# RGB_LEDs.net
KiCad netlist of a schematic drawn in Altium Designer
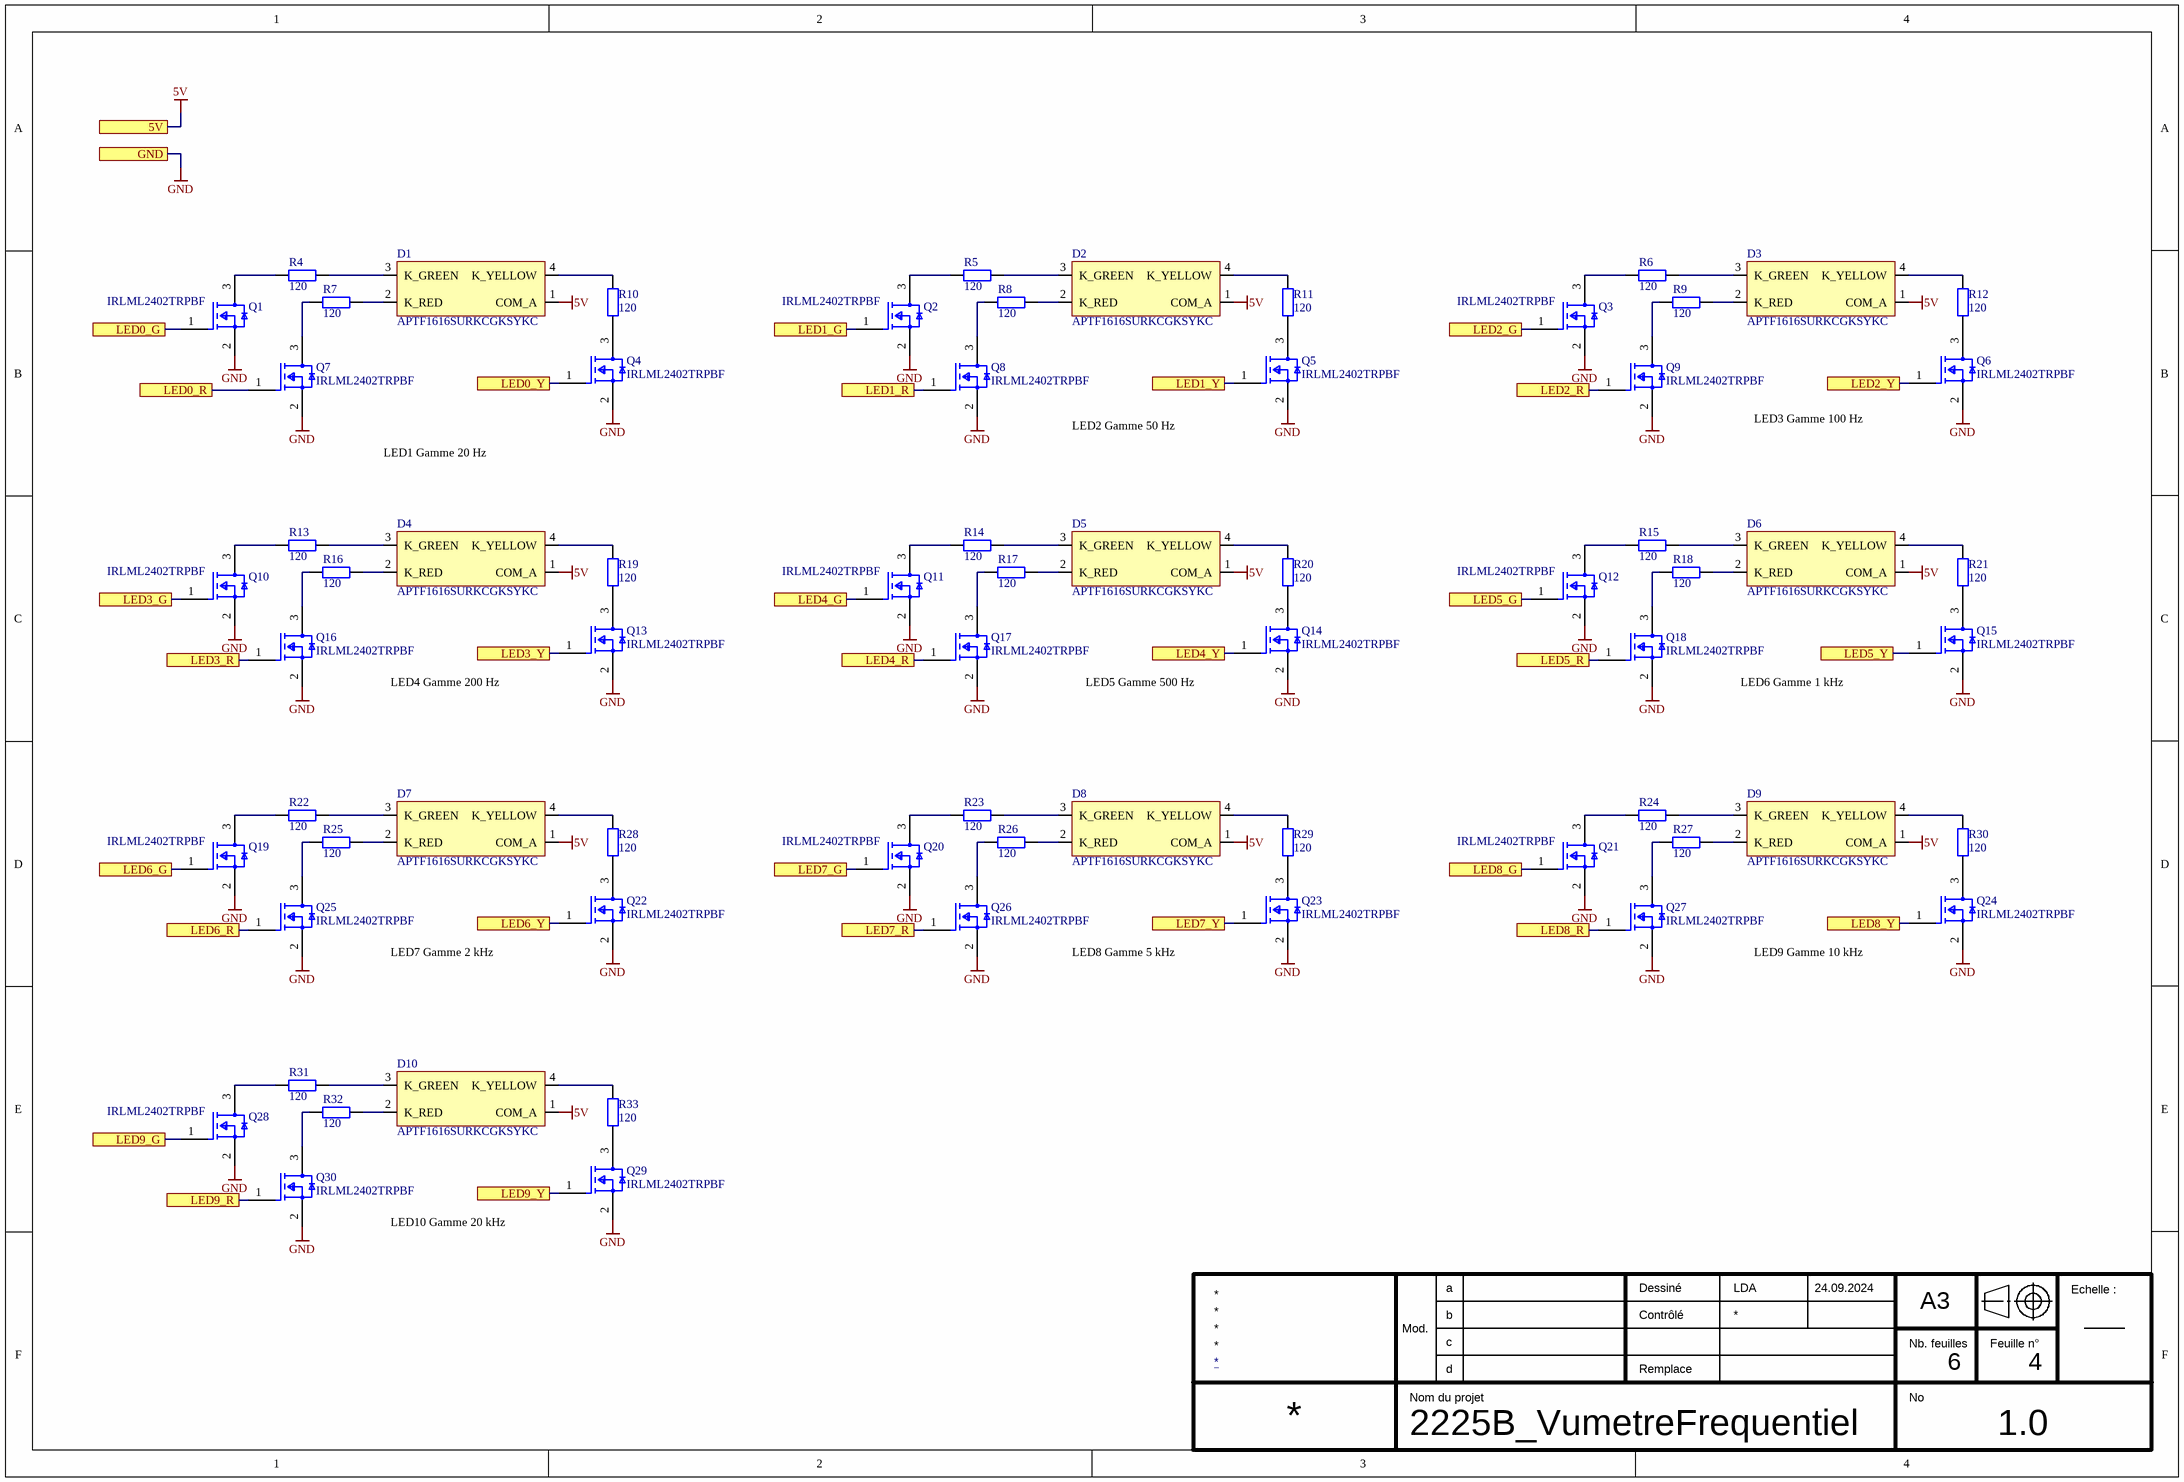
[diagram p0: RGB_LEDs.SchDoc]

(export (version "E")
  (design (tool "Eeschema 10.0.6"))
  (components
    (comp (ref "D1")
      (value "APTF1616SURKCGKSYKC")
      (footprint "APTF1616SURKCGKSYKC")
      (fields (field (name "MOUSER PART NUMBER") "604-APTF1616KCGKSYKC"))
      (libsource (lib "2225B_VumetreFrequenciel") (part "APTF1616SURKCGKSYKC"))
    )
    (comp (ref "D2")
      (value "APTF1616SURKCGKSYKC")
      (footprint "APTF1616SURKCGKSYKC")
      (fields (field (name "MOUSER PART NUMBER") "604-APTF1616KCGKSYKC"))
      (libsource (lib "2225B_VumetreFrequenciel") (part "APTF1616SURKCGKSYKC"))
    )
    (comp (ref "D3")
      (value "APTF1616SURKCGKSYKC")
      (footprint "APTF1616SURKCGKSYKC")
      (fields (field (name "MOUSER PART NUMBER") "604-APTF1616KCGKSYKC"))
      (libsource (lib "2225B_VumetreFrequenciel") (part "APTF1616SURKCGKSYKC"))
    )
    (comp (ref "D4")
      (value "APTF1616SURKCGKSYKC")
      (footprint "APTF1616SURKCGKSYKC")
      (fields (field (name "MOUSER PART NUMBER") "604-APTF1616KCGKSYKC"))
      (libsource (lib "2225B_VumetreFrequenciel") (part "APTF1616SURKCGKSYKC"))
    )
    (comp (ref "D5")
      (value "APTF1616SURKCGKSYKC")
      (footprint "APTF1616SURKCGKSYKC")
      (fields (field (name "MOUSER PART NUMBER") "604-APTF1616KCGKSYKC"))
      (libsource (lib "2225B_VumetreFrequenciel") (part "APTF1616SURKCGKSYKC"))
    )
    (comp (ref "D6")
      (value "APTF1616SURKCGKSYKC")
      (footprint "APTF1616SURKCGKSYKC")
      (fields (field (name "MOUSER PART NUMBER") "604-APTF1616KCGKSYKC"))
      (libsource (lib "2225B_VumetreFrequenciel") (part "APTF1616SURKCGKSYKC"))
    )
    (comp (ref "D7")
      (value "APTF1616SURKCGKSYKC")
      (footprint "APTF1616SURKCGKSYKC")
      (fields (field (name "MOUSER PART NUMBER") "604-APTF1616KCGKSYKC"))
      (libsource (lib "2225B_VumetreFrequenciel") (part "APTF1616SURKCGKSYKC"))
    )
    (comp (ref "D8")
      (value "APTF1616SURKCGKSYKC")
      (footprint "APTF1616SURKCGKSYKC")
      (fields (field (name "MOUSER PART NUMBER") "604-APTF1616KCGKSYKC"))
      (libsource (lib "2225B_VumetreFrequenciel") (part "APTF1616SURKCGKSYKC"))
    )
    (comp (ref "D9")
      (value "APTF1616SURKCGKSYKC")
      (footprint "APTF1616SURKCGKSYKC")
      (fields (field (name "MOUSER PART NUMBER") "604-APTF1616KCGKSYKC"))
      (libsource (lib "2225B_VumetreFrequenciel") (part "APTF1616SURKCGKSYKC"))
    )
    (comp (ref "D10")
      (value "APTF1616SURKCGKSYKC")
      (footprint "APTF1616SURKCGKSYKC")
      (fields (field (name "MOUSER PART NUMBER") "604-APTF1616KCGKSYKC"))
      (libsource (lib "2225B_VumetreFrequenciel") (part "APTF1616SURKCGKSYKC"))
    )
    (comp (ref "Q1")
      (value "IRLML2402TRPBF")
      (footprint "FP-Micro3-IPC_B")
      (description "MOSFET N-CH 20V 1.2A SOT-23")
      (libsource (lib "Altium Content Vault") (part "0a9ea7c96deaaede766a5b531c28de0"))
    )
    (comp (ref "Q2")
      (value "IRLML2402TRPBF")
      (footprint "FP-Micro3-IPC_B")
      (description "MOSFET N-CH 20V 1.2A SOT-23")
      (libsource (lib "Altium Content Vault") (part "0a9ea7c96deaaede766a5b531c28de0"))
    )
    (comp (ref "Q3")
      (value "IRLML2402TRPBF")
      (footprint "FP-Micro3-IPC_B")
      (description "MOSFET N-CH 20V 1.2A SOT-23")
      (libsource (lib "Altium Content Vault") (part "0a9ea7c96deaaede766a5b531c28de0"))
    )
    (comp (ref "Q4")
      (value "IRLML2402TRPBF")
      (footprint "FP-Micro3-IPC_B")
      (description "MOSFET N-CH 20V 1.2A SOT-23")
      (libsource (lib "Altium Content Vault") (part "0a9ea7c96deaaede766a5b531c28de0"))
    )
    (comp (ref "Q5")
      (value "IRLML2402TRPBF")
      (footprint "FP-Micro3-IPC_B")
      (description "MOSFET N-CH 20V 1.2A SOT-23")
      (libsource (lib "Altium Content Vault") (part "0a9ea7c96deaaede766a5b531c28de0"))
    )
    (comp (ref "Q6")
      (value "IRLML2402TRPBF")
      (footprint "FP-Micro3-IPC_B")
      (description "MOSFET N-CH 20V 1.2A SOT-23")
      (libsource (lib "Altium Content Vault") (part "0a9ea7c96deaaede766a5b531c28de0"))
    )
    (comp (ref "Q7")
      (value "IRLML2402TRPBF")
      (footprint "FP-Micro3-IPC_B")
      (description "MOSFET N-CH 20V 1.2A SOT-23")
      (libsource (lib "Altium Content Vault") (part "0a9ea7c96deaaede766a5b531c28de0"))
    )
    (comp (ref "Q8")
      (value "IRLML2402TRPBF")
      (footprint "FP-Micro3-IPC_B")
      (description "MOSFET N-CH 20V 1.2A SOT-23")
      (libsource (lib "Altium Content Vault") (part "0a9ea7c96deaaede766a5b531c28de0"))
    )
    (comp (ref "Q9")
      (value "IRLML2402TRPBF")
      (footprint "FP-Micro3-IPC_B")
      (description "MOSFET N-CH 20V 1.2A SOT-23")
      (libsource (lib "Altium Content Vault") (part "0a9ea7c96deaaede766a5b531c28de0"))
    )
    (comp (ref "Q10")
      (value "IRLML2402TRPBF")
      (footprint "FP-Micro3-IPC_B")
      (description "MOSFET N-CH 20V 1.2A SOT-23")
      (libsource (lib "Altium Content Vault") (part "0a9ea7c96deaaede766a5b531c28de0"))
    )
    (comp (ref "Q11")
      (value "IRLML2402TRPBF")
      (footprint "FP-Micro3-IPC_B")
      (description "MOSFET N-CH 20V 1.2A SOT-23")
      (libsource (lib "Altium Content Vault") (part "0a9ea7c96deaaede766a5b531c28de0"))
    )
    (comp (ref "Q12")
      (value "IRLML2402TRPBF")
      (footprint "FP-Micro3-IPC_B")
      (description "MOSFET N-CH 20V 1.2A SOT-23")
      (libsource (lib "Altium Content Vault") (part "0a9ea7c96deaaede766a5b531c28de0"))
    )
    (comp (ref "Q13")
      (value "IRLML2402TRPBF")
      (footprint "FP-Micro3-IPC_B")
      (description "MOSFET N-CH 20V 1.2A SOT-23")
      (libsource (lib "Altium Content Vault") (part "0a9ea7c96deaaede766a5b531c28de0"))
    )
    (comp (ref "Q14")
      (value "IRLML2402TRPBF")
      (footprint "FP-Micro3-IPC_B")
      (description "MOSFET N-CH 20V 1.2A SOT-23")
      (libsource (lib "Altium Content Vault") (part "0a9ea7c96deaaede766a5b531c28de0"))
    )
    (comp (ref "Q15")
      (value "IRLML2402TRPBF")
      (footprint "FP-Micro3-IPC_B")
      (description "MOSFET N-CH 20V 1.2A SOT-23")
      (libsource (lib "Altium Content Vault") (part "0a9ea7c96deaaede766a5b531c28de0"))
    )
    (comp (ref "Q16")
      (value "IRLML2402TRPBF")
      (footprint "FP-Micro3-IPC_B")
      (description "MOSFET N-CH 20V 1.2A SOT-23")
      (libsource (lib "Altium Content Vault") (part "0a9ea7c96deaaede766a5b531c28de0"))
    )
    (comp (ref "Q17")
      (value "IRLML2402TRPBF")
      (footprint "FP-Micro3-IPC_B")
      (description "MOSFET N-CH 20V 1.2A SOT-23")
      (libsource (lib "Altium Content Vault") (part "0a9ea7c96deaaede766a5b531c28de0"))
    )
    (comp (ref "Q18")
      (value "IRLML2402TRPBF")
      (footprint "FP-Micro3-IPC_B")
      (description "MOSFET N-CH 20V 1.2A SOT-23")
      (libsource (lib "Altium Content Vault") (part "0a9ea7c96deaaede766a5b531c28de0"))
    )
    (comp (ref "Q19")
      (value "IRLML2402TRPBF")
      (footprint "FP-Micro3-IPC_B")
      (description "MOSFET N-CH 20V 1.2A SOT-23")
      (libsource (lib "Altium Content Vault") (part "0a9ea7c96deaaede766a5b531c28de0"))
    )
    (comp (ref "Q20")
      (value "IRLML2402TRPBF")
      (footprint "FP-Micro3-IPC_B")
      (description "MOSFET N-CH 20V 1.2A SOT-23")
      (libsource (lib "Altium Content Vault") (part "0a9ea7c96deaaede766a5b531c28de0"))
    )
    (comp (ref "Q21")
      (value "IRLML2402TRPBF")
      (footprint "FP-Micro3-IPC_B")
      (description "MOSFET N-CH 20V 1.2A SOT-23")
      (libsource (lib "Altium Content Vault") (part "0a9ea7c96deaaede766a5b531c28de0"))
    )
    (comp (ref "Q22")
      (value "IRLML2402TRPBF")
      (footprint "FP-Micro3-IPC_B")
      (description "MOSFET N-CH 20V 1.2A SOT-23")
      (libsource (lib "Altium Content Vault") (part "0a9ea7c96deaaede766a5b531c28de0"))
    )
    (comp (ref "Q23")
      (value "IRLML2402TRPBF")
      (footprint "FP-Micro3-IPC_B")
      (description "MOSFET N-CH 20V 1.2A SOT-23")
      (libsource (lib "Altium Content Vault") (part "0a9ea7c96deaaede766a5b531c28de0"))
    )
    (comp (ref "Q24")
      (value "IRLML2402TRPBF")
      (footprint "FP-Micro3-IPC_B")
      (description "MOSFET N-CH 20V 1.2A SOT-23")
      (libsource (lib "Altium Content Vault") (part "0a9ea7c96deaaede766a5b531c28de0"))
    )
    (comp (ref "Q25")
      (value "IRLML2402TRPBF")
      (footprint "FP-Micro3-IPC_B")
      (description "MOSFET N-CH 20V 1.2A SOT-23")
      (libsource (lib "Altium Content Vault") (part "0a9ea7c96deaaede766a5b531c28de0"))
    )
    (comp (ref "Q26")
      (value "IRLML2402TRPBF")
      (footprint "FP-Micro3-IPC_B")
      (description "MOSFET N-CH 20V 1.2A SOT-23")
      (libsource (lib "Altium Content Vault") (part "0a9ea7c96deaaede766a5b531c28de0"))
    )
    (comp (ref "Q27")
      (value "IRLML2402TRPBF")
      (footprint "FP-Micro3-IPC_B")
      (description "MOSFET N-CH 20V 1.2A SOT-23")
      (libsource (lib "Altium Content Vault") (part "0a9ea7c96deaaede766a5b531c28de0"))
    )
    (comp (ref "Q28")
      (value "IRLML2402TRPBF")
      (footprint "FP-Micro3-IPC_B")
      (description "MOSFET N-CH 20V 1.2A SOT-23")
      (libsource (lib "Altium Content Vault") (part "0a9ea7c96deaaede766a5b531c28de0"))
    )
    (comp (ref "Q29")
      (value "IRLML2402TRPBF")
      (footprint "FP-Micro3-IPC_B")
      (description "MOSFET N-CH 20V 1.2A SOT-23")
      (libsource (lib "Altium Content Vault") (part "0a9ea7c96deaaede766a5b531c28de0"))
    )
    (comp (ref "Q30")
      (value "IRLML2402TRPBF")
      (footprint "FP-Micro3-IPC_B")
      (description "MOSFET N-CH 20V 1.2A SOT-23")
      (libsource (lib "Altium Content Vault") (part "0a9ea7c96deaaede766a5b531c28de0"))
    )
    (comp (ref "R4")
      (value "120")
      (footprint "RESC2012X06M")
      (description "Resistor")
      (fields (field (name "PUBLISHER") "Altium Limited"))
      (libsource (lib "Miscellaneous Devices") (part "Res2"))
    )
    (comp (ref "R5")
      (value "120")
      (footprint "RESC2012X06M")
      (description "Resistor")
      (fields (field (name "PUBLISHER") "Altium Limited"))
      (libsource (lib "Miscellaneous Devices") (part "Res2"))
    )
    (comp (ref "R6")
      (value "120")
      (footprint "RESC2012X06M")
      (description "Resistor")
      (fields (field (name "PUBLISHER") "Altium Limited"))
      (libsource (lib "Miscellaneous Devices") (part "Res2"))
    )
    (comp (ref "R7")
      (value "120")
      (footprint "RESC2012X06M")
      (description "Resistor")
      (fields (field (name "PUBLISHER") "Altium Limited"))
      (libsource (lib "Miscellaneous Devices") (part "Res2"))
    )
    (comp (ref "R8")
      (value "120")
      (footprint "RESC2012X06M")
      (description "Resistor")
      (fields (field (name "PUBLISHER") "Altium Limited"))
      (libsource (lib "Miscellaneous Devices") (part "Res2"))
    )
    (comp (ref "R9")
      (value "120")
      (footprint "RESC2012X06M")
      (description "Resistor")
      (fields (field (name "PUBLISHER") "Altium Limited"))
      (libsource (lib "Miscellaneous Devices") (part "Res2"))
    )
    (comp (ref "R10")
      (value "120")
      (footprint "RESC2012X06M")
      (description "Resistor")
      (fields (field (name "PUBLISHER") "Altium Limited"))
      (libsource (lib "") (part "Res2_1"))
    )
    (comp (ref "R11")
      (value "120")
      (footprint "RESC2012X06M")
      (description "Resistor")
      (fields (field (name "PUBLISHER") "Altium Limited"))
      (libsource (lib "") (part "Res2_1"))
    )
    (comp (ref "R12")
      (value "120")
      (footprint "RESC2012X06M")
      (description "Resistor")
      (fields (field (name "PUBLISHER") "Altium Limited"))
      (libsource (lib "") (part "Res2_1"))
    )
    (comp (ref "R13")
      (value "120")
      (footprint "RESC2012X06M")
      (description "Resistor")
      (fields (field (name "PUBLISHER") "Altium Limited"))
      (libsource (lib "Miscellaneous Devices") (part "Res2"))
    )
    (comp (ref "R14")
      (value "120")
      (footprint "RESC2012X06M")
      (description "Resistor")
      (fields (field (name "PUBLISHER") "Altium Limited"))
      (libsource (lib "Miscellaneous Devices") (part "Res2"))
    )
    (comp (ref "R15")
      (value "120")
      (footprint "RESC2012X06M")
      (description "Resistor")
      (fields (field (name "PUBLISHER") "Altium Limited"))
      (libsource (lib "Miscellaneous Devices") (part "Res2"))
    )
    (comp (ref "R16")
      (value "120")
      (footprint "RESC2012X06M")
      (description "Resistor")
      (fields (field (name "PUBLISHER") "Altium Limited"))
      (libsource (lib "Miscellaneous Devices") (part "Res2"))
    )
    (comp (ref "R17")
      (value "120")
      (footprint "RESC2012X06M")
      (description "Resistor")
      (fields (field (name "PUBLISHER") "Altium Limited"))
      (libsource (lib "Miscellaneous Devices") (part "Res2"))
    )
    (comp (ref "R18")
      (value "120")
      (footprint "RESC2012X06M")
      (description "Resistor")
      (fields (field (name "PUBLISHER") "Altium Limited"))
      (libsource (lib "Miscellaneous Devices") (part "Res2"))
    )
    (comp (ref "R19")
      (value "120")
      (footprint "RESC2012X06M")
      (description "Resistor")
      (fields (field (name "PUBLISHER") "Altium Limited"))
      (libsource (lib "") (part "Res2_1"))
    )
    (comp (ref "R20")
      (value "120")
      (footprint "RESC2012X06M")
      (description "Resistor")
      (fields (field (name "PUBLISHER") "Altium Limited"))
      (libsource (lib "") (part "Res2_1"))
    )
    (comp (ref "R21")
      (value "120")
      (footprint "RESC2012X06M")
      (description "Resistor")
      (fields (field (name "PUBLISHER") "Altium Limited"))
      (libsource (lib "") (part "Res2_1"))
    )
    (comp (ref "R22")
      (value "120")
      (footprint "RESC2012X06M")
      (description "Resistor")
      (fields (field (name "PUBLISHER") "Altium Limited"))
      (libsource (lib "Miscellaneous Devices") (part "Res2"))
    )
    (comp (ref "R23")
      (value "120")
      (footprint "RESC2012X06M")
      (description "Resistor")
      (fields (field (name "PUBLISHER") "Altium Limited"))
      (libsource (lib "Miscellaneous Devices") (part "Res2"))
    )
    (comp (ref "R24")
      (value "120")
      (footprint "RESC2012X06M")
      (description "Resistor")
      (fields (field (name "PUBLISHER") "Altium Limited"))
      (libsource (lib "Miscellaneous Devices") (part "Res2"))
    )
    (comp (ref "R25")
      (value "120")
      (footprint "RESC2012X06M")
      (description "Resistor")
      (fields (field (name "PUBLISHER") "Altium Limited"))
      (libsource (lib "Miscellaneous Devices") (part "Res2"))
    )
    (comp (ref "R26")
      (value "120")
      (footprint "RESC2012X06M")
      (description "Resistor")
      (fields (field (name "PUBLISHER") "Altium Limited"))
      (libsource (lib "Miscellaneous Devices") (part "Res2"))
    )
    (comp (ref "R27")
      (value "120")
      (footprint "RESC2012X06M")
      (description "Resistor")
      (fields (field (name "PUBLISHER") "Altium Limited"))
      (libsource (lib "Miscellaneous Devices") (part "Res2"))
    )
    (comp (ref "R28")
      (value "120")
      (footprint "RESC2012X06M")
      (description "Resistor")
      (fields (field (name "PUBLISHER") "Altium Limited"))
      (libsource (lib "") (part "Res2_1"))
    )
    (comp (ref "R29")
      (value "120")
      (footprint "RESC2012X06M")
      (description "Resistor")
      (fields (field (name "PUBLISHER") "Altium Limited"))
      (libsource (lib "") (part "Res2_1"))
    )
    (comp (ref "R30")
      (value "120")
      (footprint "RESC2012X06M")
      (description "Resistor")
      (fields (field (name "PUBLISHER") "Altium Limited"))
      (libsource (lib "") (part "Res2_1"))
    )
    (comp (ref "R31")
      (value "120")
      (footprint "RESC2012X06M")
      (description "Resistor")
      (fields (field (name "PUBLISHER") "Altium Limited"))
      (libsource (lib "Miscellaneous Devices") (part "Res2"))
    )
    (comp (ref "R32")
      (value "120")
      (footprint "RESC2012X06M")
      (description "Resistor")
      (fields (field (name "PUBLISHER") "Altium Limited"))
      (libsource (lib "Miscellaneous Devices") (part "Res2"))
    )
    (comp (ref "R33")
      (value "120")
      (footprint "RESC2012X06M")
      (description "Resistor")
      (fields (field (name "PUBLISHER") "Altium Limited"))
      (libsource (lib "") (part "Res2_1"))
    )
  )
  (nets
    (net (code "1") (name "/LED0_G") (class "Default")
      (node (ref "Q1") (pin "1") (pinfunction "G_1") (pintype "passive"))
    )
    (net (code "2") (name "/LED0_R") (class "Default")
      (node (ref "Q7") (pin "1") (pinfunction "G_1") (pintype "passive"))
    )
    (net (code "3") (name "/LED0_Y") (class "Default")
      (node (ref "Q4") (pin "1") (pinfunction "G_1") (pintype "passive"))
    )
    (net (code "4") (name "/LED1_G") (class "Default")
      (node (ref "Q2") (pin "1") (pinfunction "G_1") (pintype "passive"))
    )
    (net (code "5") (name "/LED1_R") (class "Default")
      (node (ref "Q8") (pin "1") (pinfunction "G_1") (pintype "passive"))
    )
    (net (code "6") (name "/LED1_Y") (class "Default")
      (node (ref "Q5") (pin "1") (pinfunction "G_1") (pintype "passive"))
    )
    (net (code "7") (name "/LED2_G") (class "Default")
      (node (ref "Q3") (pin "1") (pinfunction "G_1") (pintype "passive"))
    )
    (net (code "8") (name "/LED2_R") (class "Default")
      (node (ref "Q9") (pin "1") (pinfunction "G_1") (pintype "passive"))
    )
    (net (code "9") (name "/LED2_Y") (class "Default")
      (node (ref "Q6") (pin "1") (pinfunction "G_1") (pintype "passive"))
    )
    (net (code "10") (name "/LED3_G") (class "Default")
      (node (ref "Q10") (pin "1") (pinfunction "G_1") (pintype "passive"))
    )
    (net (code "11") (name "/LED3_R") (class "Default")
      (node (ref "Q16") (pin "1") (pinfunction "G_1") (pintype "passive"))
    )
    (net (code "12") (name "/LED3_Y") (class "Default")
      (node (ref "Q13") (pin "1") (pinfunction "G_1") (pintype "passive"))
    )
    (net (code "13") (name "/LED4_G") (class "Default")
      (node (ref "Q11") (pin "1") (pinfunction "G_1") (pintype "passive"))
    )
    (net (code "14") (name "/LED4_R") (class "Default")
      (node (ref "Q17") (pin "1") (pinfunction "G_1") (pintype "passive"))
    )
    (net (code "15") (name "/LED4_Y") (class "Default")
      (node (ref "Q14") (pin "1") (pinfunction "G_1") (pintype "passive"))
    )
    (net (code "16") (name "/LED5_G") (class "Default")
      (node (ref "Q12") (pin "1") (pinfunction "G_1") (pintype "passive"))
    )
    (net (code "17") (name "/LED5_R") (class "Default")
      (node (ref "Q18") (pin "1") (pinfunction "G_1") (pintype "passive"))
    )
    (net (code "18") (name "/LED5_Y") (class "Default")
      (node (ref "Q15") (pin "1") (pinfunction "G_1") (pintype "passive"))
    )
    (net (code "19") (name "/LED6_G") (class "Default")
      (node (ref "Q19") (pin "1") (pinfunction "G_1") (pintype "passive"))
    )
    (net (code "20") (name "/LED6_R") (class "Default")
      (node (ref "Q25") (pin "1") (pinfunction "G_1") (pintype "passive"))
    )
    (net (code "21") (name "/LED6_Y") (class "Default")
      (node (ref "Q22") (pin "1") (pinfunction "G_1") (pintype "passive"))
    )
    (net (code "22") (name "/LED7_G") (class "Default")
      (node (ref "Q20") (pin "1") (pinfunction "G_1") (pintype "passive"))
    )
    (net (code "23") (name "/LED7_R") (class "Default")
      (node (ref "Q26") (pin "1") (pinfunction "G_1") (pintype "passive"))
    )
    (net (code "24") (name "/LED7_Y") (class "Default")
      (node (ref "Q23") (pin "1") (pinfunction "G_1") (pintype "passive"))
    )
    (net (code "25") (name "/LED8_G") (class "Default")
      (node (ref "Q21") (pin "1") (pinfunction "G_1") (pintype "passive"))
    )
    (net (code "26") (name "/LED8_R") (class "Default")
      (node (ref "Q27") (pin "1") (pinfunction "G_1") (pintype "passive"))
    )
    (net (code "27") (name "/LED8_Y") (class "Default")
      (node (ref "Q24") (pin "1") (pinfunction "G_1") (pintype "passive"))
    )
    (net (code "28") (name "/LED9_G") (class "Default")
      (node (ref "Q28") (pin "1") (pinfunction "G_1") (pintype "passive"))
    )
    (net (code "29") (name "/LED9_R") (class "Default")
      (node (ref "Q30") (pin "1") (pinfunction "G_1") (pintype "passive"))
    )
    (net (code "30") (name "/LED9_Y") (class "Default")
      (node (ref "Q29") (pin "1") (pinfunction "G_1") (pintype "passive"))
    )
    (net (code "31") (name "5V") (class "Default")
      (node (ref "D1") (pin "1") (pinfunction "COM_A_1") (pintype "passive"))
      (node (ref "D10") (pin "1") (pinfunction "COM_A_1") (pintype "passive"))
      (node (ref "D2") (pin "1") (pinfunction "COM_A_1") (pintype "passive"))
      (node (ref "D3") (pin "1") (pinfunction "COM_A_1") (pintype "passive"))
      (node (ref "D4") (pin "1") (pinfunction "COM_A_1") (pintype "passive"))
      (node (ref "D5") (pin "1") (pinfunction "COM_A_1") (pintype "passive"))
      (node (ref "D6") (pin "1") (pinfunction "COM_A_1") (pintype "passive"))
      (node (ref "D7") (pin "1") (pinfunction "COM_A_1") (pintype "passive"))
      (node (ref "D8") (pin "1") (pinfunction "COM_A_1") (pintype "passive"))
      (node (ref "D9") (pin "1") (pinfunction "COM_A_1") (pintype "passive"))
    )
    (net (code "32") (name "GND") (class "Default")
      (node (ref "Q1") (pin "2") (pinfunction "S_2") (pintype "passive"))
      (node (ref "Q10") (pin "2") (pinfunction "S_2") (pintype "passive"))
      (node (ref "Q11") (pin "2") (pinfunction "S_2") (pintype "passive"))
      (node (ref "Q12") (pin "2") (pinfunction "S_2") (pintype "passive"))
      (node (ref "Q13") (pin "2") (pinfunction "S_2") (pintype "passive"))
      (node (ref "Q14") (pin "2") (pinfunction "S_2") (pintype "passive"))
      (node (ref "Q15") (pin "2") (pinfunction "S_2") (pintype "passive"))
      (node (ref "Q16") (pin "2") (pinfunction "S_2") (pintype "passive"))
      (node (ref "Q17") (pin "2") (pinfunction "S_2") (pintype "passive"))
      (node (ref "Q18") (pin "2") (pinfunction "S_2") (pintype "passive"))
      (node (ref "Q19") (pin "2") (pinfunction "S_2") (pintype "passive"))
      (node (ref "Q2") (pin "2") (pinfunction "S_2") (pintype "passive"))
      (node (ref "Q20") (pin "2") (pinfunction "S_2") (pintype "passive"))
      (node (ref "Q21") (pin "2") (pinfunction "S_2") (pintype "passive"))
      (node (ref "Q22") (pin "2") (pinfunction "S_2") (pintype "passive"))
      (node (ref "Q23") (pin "2") (pinfunction "S_2") (pintype "passive"))
      (node (ref "Q24") (pin "2") (pinfunction "S_2") (pintype "passive"))
      (node (ref "Q25") (pin "2") (pinfunction "S_2") (pintype "passive"))
      (node (ref "Q26") (pin "2") (pinfunction "S_2") (pintype "passive"))
      (node (ref "Q27") (pin "2") (pinfunction "S_2") (pintype "passive"))
      (node (ref "Q28") (pin "2") (pinfunction "S_2") (pintype "passive"))
      (node (ref "Q29") (pin "2") (pinfunction "S_2") (pintype "passive"))
      (node (ref "Q3") (pin "2") (pinfunction "S_2") (pintype "passive"))
      (node (ref "Q30") (pin "2") (pinfunction "S_2") (pintype "passive"))
      (node (ref "Q4") (pin "2") (pinfunction "S_2") (pintype "passive"))
      (node (ref "Q5") (pin "2") (pinfunction "S_2") (pintype "passive"))
      (node (ref "Q6") (pin "2") (pinfunction "S_2") (pintype "passive"))
      (node (ref "Q7") (pin "2") (pinfunction "S_2") (pintype "passive"))
      (node (ref "Q8") (pin "2") (pinfunction "S_2") (pintype "passive"))
      (node (ref "Q9") (pin "2") (pinfunction "S_2") (pintype "passive"))
    )
    (net (code "33") (name "Net-(D1-K_GREEN)") (class "Default")
      (node (ref "D1") (pin "3") (pinfunction "K_GREEN_3") (pintype "passive"))
      (node (ref "R4") (pin "1") (pinfunction "1_1") (pintype "passive"))
    )
    (net (code "34") (name "Net-(D1-K_RED)") (class "Default")
      (node (ref "D1") (pin "2") (pinfunction "K_RED_2") (pintype "passive"))
      (node (ref "R7") (pin "1") (pinfunction "1_1") (pintype "passive"))
    )
    (net (code "35") (name "Net-(D1-K_YELLOW)") (class "Default")
      (node (ref "D1") (pin "4") (pinfunction "K_YELLOW_4") (pintype "passive"))
      (node (ref "R10") (pin "1") (pinfunction "1_1") (pintype "passive"))
    )
    (net (code "36") (name "Net-(D2-K_GREEN)") (class "Default")
      (node (ref "D2") (pin "3") (pinfunction "K_GREEN_3") (pintype "passive"))
      (node (ref "R5") (pin "1") (pinfunction "1_1") (pintype "passive"))
    )
    (net (code "37") (name "Net-(D2-K_RED)") (class "Default")
      (node (ref "D2") (pin "2") (pinfunction "K_RED_2") (pintype "passive"))
      (node (ref "R8") (pin "1") (pinfunction "1_1") (pintype "passive"))
    )
    (net (code "38") (name "Net-(D2-K_YELLOW)") (class "Default")
      (node (ref "D2") (pin "4") (pinfunction "K_YELLOW_4") (pintype "passive"))
      (node (ref "R11") (pin "1") (pinfunction "1_1") (pintype "passive"))
    )
    (net (code "39") (name "Net-(D3-K_GREEN)") (class "Default")
      (node (ref "D3") (pin "3") (pinfunction "K_GREEN_3") (pintype "passive"))
      (node (ref "R6") (pin "1") (pinfunction "1_1") (pintype "passive"))
    )
    (net (code "40") (name "Net-(D3-K_RED)") (class "Default")
      (node (ref "D3") (pin "2") (pinfunction "K_RED_2") (pintype "passive"))
      (node (ref "R9") (pin "1") (pinfunction "1_1") (pintype "passive"))
    )
    (net (code "41") (name "Net-(D3-K_YELLOW)") (class "Default")
      (node (ref "D3") (pin "4") (pinfunction "K_YELLOW_4") (pintype "passive"))
      (node (ref "R12") (pin "1") (pinfunction "1_1") (pintype "passive"))
    )
    (net (code "42") (name "Net-(D4-K_GREEN)") (class "Default")
      (node (ref "D4") (pin "3") (pinfunction "K_GREEN_3") (pintype "passive"))
      (node (ref "R13") (pin "1") (pinfunction "1_1") (pintype "passive"))
    )
    (net (code "43") (name "Net-(D4-K_RED)") (class "Default")
      (node (ref "D4") (pin "2") (pinfunction "K_RED_2") (pintype "passive"))
      (node (ref "R16") (pin "1") (pinfunction "1_1") (pintype "passive"))
    )
    (net (code "44") (name "Net-(D4-K_YELLOW)") (class "Default")
      (node (ref "D4") (pin "4") (pinfunction "K_YELLOW_4") (pintype "passive"))
      (node (ref "R19") (pin "1") (pinfunction "1_1") (pintype "passive"))
    )
    (net (code "45") (name "Net-(D5-K_GREEN)") (class "Default")
      (node (ref "D5") (pin "3") (pinfunction "K_GREEN_3") (pintype "passive"))
      (node (ref "R14") (pin "1") (pinfunction "1_1") (pintype "passive"))
    )
    (net (code "46") (name "Net-(D5-K_RED)") (class "Default")
      (node (ref "D5") (pin "2") (pinfunction "K_RED_2") (pintype "passive"))
      (node (ref "R17") (pin "1") (pinfunction "1_1") (pintype "passive"))
    )
    (net (code "47") (name "Net-(D5-K_YELLOW)") (class "Default")
      (node (ref "D5") (pin "4") (pinfunction "K_YELLOW_4") (pintype "passive"))
      (node (ref "R20") (pin "1") (pinfunction "1_1") (pintype "passive"))
    )
    (net (code "48") (name "Net-(D6-K_GREEN)") (class "Default")
      (node (ref "D6") (pin "3") (pinfunction "K_GREEN_3") (pintype "passive"))
      (node (ref "R15") (pin "1") (pinfunction "1_1") (pintype "passive"))
    )
    (net (code "49") (name "Net-(D6-K_RED)") (class "Default")
      (node (ref "D6") (pin "2") (pinfunction "K_RED_2") (pintype "passive"))
      (node (ref "R18") (pin "1") (pinfunction "1_1") (pintype "passive"))
    )
    (net (code "50") (name "Net-(D6-K_YELLOW)") (class "Default")
      (node (ref "D6") (pin "4") (pinfunction "K_YELLOW_4") (pintype "passive"))
      (node (ref "R21") (pin "1") (pinfunction "1_1") (pintype "passive"))
    )
    (net (code "51") (name "Net-(D7-K_GREEN)") (class "Default")
      (node (ref "D7") (pin "3") (pinfunction "K_GREEN_3") (pintype "passive"))
      (node (ref "R22") (pin "1") (pinfunction "1_1") (pintype "passive"))
    )
    (net (code "52") (name "Net-(D7-K_RED)") (class "Default")
      (node (ref "D7") (pin "2") (pinfunction "K_RED_2") (pintype "passive"))
      (node (ref "R25") (pin "1") (pinfunction "1_1") (pintype "passive"))
    )
    (net (code "53") (name "Net-(D7-K_YELLOW)") (class "Default")
      (node (ref "D7") (pin "4") (pinfunction "K_YELLOW_4") (pintype "passive"))
      (node (ref "R28") (pin "1") (pinfunction "1_1") (pintype "passive"))
    )
    (net (code "54") (name "Net-(D8-K_GREEN)") (class "Default")
      (node (ref "D8") (pin "3") (pinfunction "K_GREEN_3") (pintype "passive"))
      (node (ref "R23") (pin "1") (pinfunction "1_1") (pintype "passive"))
    )
    (net (code "55") (name "Net-(D8-K_RED)") (class "Default")
      (node (ref "D8") (pin "2") (pinfunction "K_RED_2") (pintype "passive"))
      (node (ref "R26") (pin "1") (pinfunction "1_1") (pintype "passive"))
    )
    (net (code "56") (name "Net-(D8-K_YELLOW)") (class "Default")
      (node (ref "D8") (pin "4") (pinfunction "K_YELLOW_4") (pintype "passive"))
      (node (ref "R29") (pin "1") (pinfunction "1_1") (pintype "passive"))
    )
    (net (code "57") (name "Net-(D9-K_GREEN)") (class "Default")
      (node (ref "D9") (pin "3") (pinfunction "K_GREEN_3") (pintype "passive"))
      (node (ref "R24") (pin "1") (pinfunction "1_1") (pintype "passive"))
    )
    (net (code "58") (name "Net-(D9-K_RED)") (class "Default")
      (node (ref "D9") (pin "2") (pinfunction "K_RED_2") (pintype "passive"))
      (node (ref "R27") (pin "1") (pinfunction "1_1") (pintype "passive"))
    )
    (net (code "59") (name "Net-(D9-K_YELLOW)") (class "Default")
      (node (ref "D9") (pin "4") (pinfunction "K_YELLOW_4") (pintype "passive"))
      (node (ref "R30") (pin "1") (pinfunction "1_1") (pintype "passive"))
    )
    (net (code "60") (name "Net-(D10-K_GREEN)") (class "Default")
      (node (ref "D10") (pin "3") (pinfunction "K_GREEN_3") (pintype "passive"))
      (node (ref "R31") (pin "1") (pinfunction "1_1") (pintype "passive"))
    )
    (net (code "61") (name "Net-(D10-K_RED)") (class "Default")
      (node (ref "D10") (pin "2") (pinfunction "K_RED_2") (pintype "passive"))
      (node (ref "R32") (pin "1") (pinfunction "1_1") (pintype "passive"))
    )
    (net (code "62") (name "Net-(D10-K_YELLOW)") (class "Default")
      (node (ref "D10") (pin "4") (pinfunction "K_YELLOW_4") (pintype "passive"))
      (node (ref "R33") (pin "1") (pinfunction "1_1") (pintype "passive"))
    )
    (net (code "63") (name "Net-(Q1-D)") (class "Default")
      (node (ref "Q1") (pin "3") (pinfunction "D_3") (pintype "passive"))
      (node (ref "R4") (pin "2") (pinfunction "2_2") (pintype "passive"))
    )
    (net (code "64") (name "Net-(Q2-D)") (class "Default")
      (node (ref "Q2") (pin "3") (pinfunction "D_3") (pintype "passive"))
      (node (ref "R5") (pin "2") (pinfunction "2_2") (pintype "passive"))
    )
    (net (code "65") (name "Net-(Q3-D)") (class "Default")
      (node (ref "Q3") (pin "3") (pinfunction "D_3") (pintype "passive"))
      (node (ref "R6") (pin "2") (pinfunction "2_2") (pintype "passive"))
    )
    (net (code "66") (name "Net-(Q4-D)") (class "Default")
      (node (ref "Q4") (pin "3") (pinfunction "D_3") (pintype "passive"))
      (node (ref "R10") (pin "2") (pinfunction "2_2") (pintype "passive"))
    )
    (net (code "67") (name "Net-(Q5-D)") (class "Default")
      (node (ref "Q5") (pin "3") (pinfunction "D_3") (pintype "passive"))
      (node (ref "R11") (pin "2") (pinfunction "2_2") (pintype "passive"))
    )
    (net (code "68") (name "Net-(Q6-D)") (class "Default")
      (node (ref "Q6") (pin "3") (pinfunction "D_3") (pintype "passive"))
      (node (ref "R12") (pin "2") (pinfunction "2_2") (pintype "passive"))
    )
    (net (code "69") (name "Net-(Q7-D)") (class "Default")
      (node (ref "Q7") (pin "3") (pinfunction "D_3") (pintype "passive"))
      (node (ref "R7") (pin "2") (pinfunction "2_2") (pintype "passive"))
    )
    (net (code "70") (name "Net-(Q8-D)") (class "Default")
      (node (ref "Q8") (pin "3") (pinfunction "D_3") (pintype "passive"))
      (node (ref "R8") (pin "2") (pinfunction "2_2") (pintype "passive"))
    )
    (net (code "71") (name "Net-(Q9-D)") (class "Default")
      (node (ref "Q9") (pin "3") (pinfunction "D_3") (pintype "passive"))
      (node (ref "R9") (pin "2") (pinfunction "2_2") (pintype "passive"))
    )
    (net (code "72") (name "Net-(Q10-D)") (class "Default")
      (node (ref "Q10") (pin "3") (pinfunction "D_3") (pintype "passive"))
      (node (ref "R13") (pin "2") (pinfunction "2_2") (pintype "passive"))
    )
    (net (code "73") (name "Net-(Q11-D)") (class "Default")
      (node (ref "Q11") (pin "3") (pinfunction "D_3") (pintype "passive"))
      (node (ref "R14") (pin "2") (pinfunction "2_2") (pintype "passive"))
    )
    (net (code "74") (name "Net-(Q12-D)") (class "Default")
      (node (ref "Q12") (pin "3") (pinfunction "D_3") (pintype "passive"))
      (node (ref "R15") (pin "2") (pinfunction "2_2") (pintype "passive"))
    )
    (net (code "75") (name "Net-(Q13-D)") (class "Default")
      (node (ref "Q13") (pin "3") (pinfunction "D_3") (pintype "passive"))
      (node (ref "R19") (pin "2") (pinfunction "2_2") (pintype "passive"))
    )
    (net (code "76") (name "Net-(Q14-D)") (class "Default")
      (node (ref "Q14") (pin "3") (pinfunction "D_3") (pintype "passive"))
      (node (ref "R20") (pin "2") (pinfunction "2_2") (pintype "passive"))
    )
    (net (code "77") (name "Net-(Q15-D)") (class "Default")
      (node (ref "Q15") (pin "3") (pinfunction "D_3") (pintype "passive"))
      (node (ref "R21") (pin "2") (pinfunction "2_2") (pintype "passive"))
    )
    (net (code "78") (name "Net-(Q16-D)") (class "Default")
      (node (ref "Q16") (pin "3") (pinfunction "D_3") (pintype "passive"))
      (node (ref "R16") (pin "2") (pinfunction "2_2") (pintype "passive"))
    )
    (net (code "79") (name "Net-(Q17-D)") (class "Default")
      (node (ref "Q17") (pin "3") (pinfunction "D_3") (pintype "passive"))
      (node (ref "R17") (pin "2") (pinfunction "2_2") (pintype "passive"))
    )
    (net (code "80") (name "Net-(Q18-D)") (class "Default")
      (node (ref "Q18") (pin "3") (pinfunction "D_3") (pintype "passive"))
      (node (ref "R18") (pin "2") (pinfunction "2_2") (pintype "passive"))
    )
    (net (code "81") (name "Net-(Q19-D)") (class "Default")
      (node (ref "Q19") (pin "3") (pinfunction "D_3") (pintype "passive"))
      (node (ref "R22") (pin "2") (pinfunction "2_2") (pintype "passive"))
    )
    (net (code "82") (name "Net-(Q20-D)") (class "Default")
      (node (ref "Q20") (pin "3") (pinfunction "D_3") (pintype "passive"))
      (node (ref "R23") (pin "2") (pinfunction "2_2") (pintype "passive"))
    )
    (net (code "83") (name "Net-(Q21-D)") (class "Default")
      (node (ref "Q21") (pin "3") (pinfunction "D_3") (pintype "passive"))
      (node (ref "R24") (pin "2") (pinfunction "2_2") (pintype "passive"))
    )
    (net (code "84") (name "Net-(Q22-D)") (class "Default")
      (node (ref "Q22") (pin "3") (pinfunction "D_3") (pintype "passive"))
      (node (ref "R28") (pin "2") (pinfunction "2_2") (pintype "passive"))
    )
    (net (code "85") (name "Net-(Q23-D)") (class "Default")
      (node (ref "Q23") (pin "3") (pinfunction "D_3") (pintype "passive"))
      (node (ref "R29") (pin "2") (pinfunction "2_2") (pintype "passive"))
    )
    (net (code "86") (name "Net-(Q24-D)") (class "Default")
      (node (ref "Q24") (pin "3") (pinfunction "D_3") (pintype "passive"))
      (node (ref "R30") (pin "2") (pinfunction "2_2") (pintype "passive"))
    )
    (net (code "87") (name "Net-(Q25-D)") (class "Default")
      (node (ref "Q25") (pin "3") (pinfunction "D_3") (pintype "passive"))
      (node (ref "R25") (pin "2") (pinfunction "2_2") (pintype "passive"))
    )
    (net (code "88") (name "Net-(Q26-D)") (class "Default")
      (node (ref "Q26") (pin "3") (pinfunction "D_3") (pintype "passive"))
      (node (ref "R26") (pin "2") (pinfunction "2_2") (pintype "passive"))
    )
    (net (code "89") (name "Net-(Q27-D)") (class "Default")
      (node (ref "Q27") (pin "3") (pinfunction "D_3") (pintype "passive"))
      (node (ref "R27") (pin "2") (pinfunction "2_2") (pintype "passive"))
    )
    (net (code "90") (name "Net-(Q28-D)") (class "Default")
      (node (ref "Q28") (pin "3") (pinfunction "D_3") (pintype "passive"))
      (node (ref "R31") (pin "2") (pinfunction "2_2") (pintype "passive"))
    )
    (net (code "91") (name "Net-(Q29-D)") (class "Default")
      (node (ref "Q29") (pin "3") (pinfunction "D_3") (pintype "passive"))
      (node (ref "R33") (pin "2") (pinfunction "2_2") (pintype "passive"))
    )
    (net (code "92") (name "Net-(Q30-D)") (class "Default")
      (node (ref "Q30") (pin "3") (pinfunction "D_3") (pintype "passive"))
      (node (ref "R32") (pin "2") (pinfunction "2_2") (pintype "passive"))
    )
  )
)
